# con-left-bot.net
KiCad netlist of a schematic drawn in Altium Designer
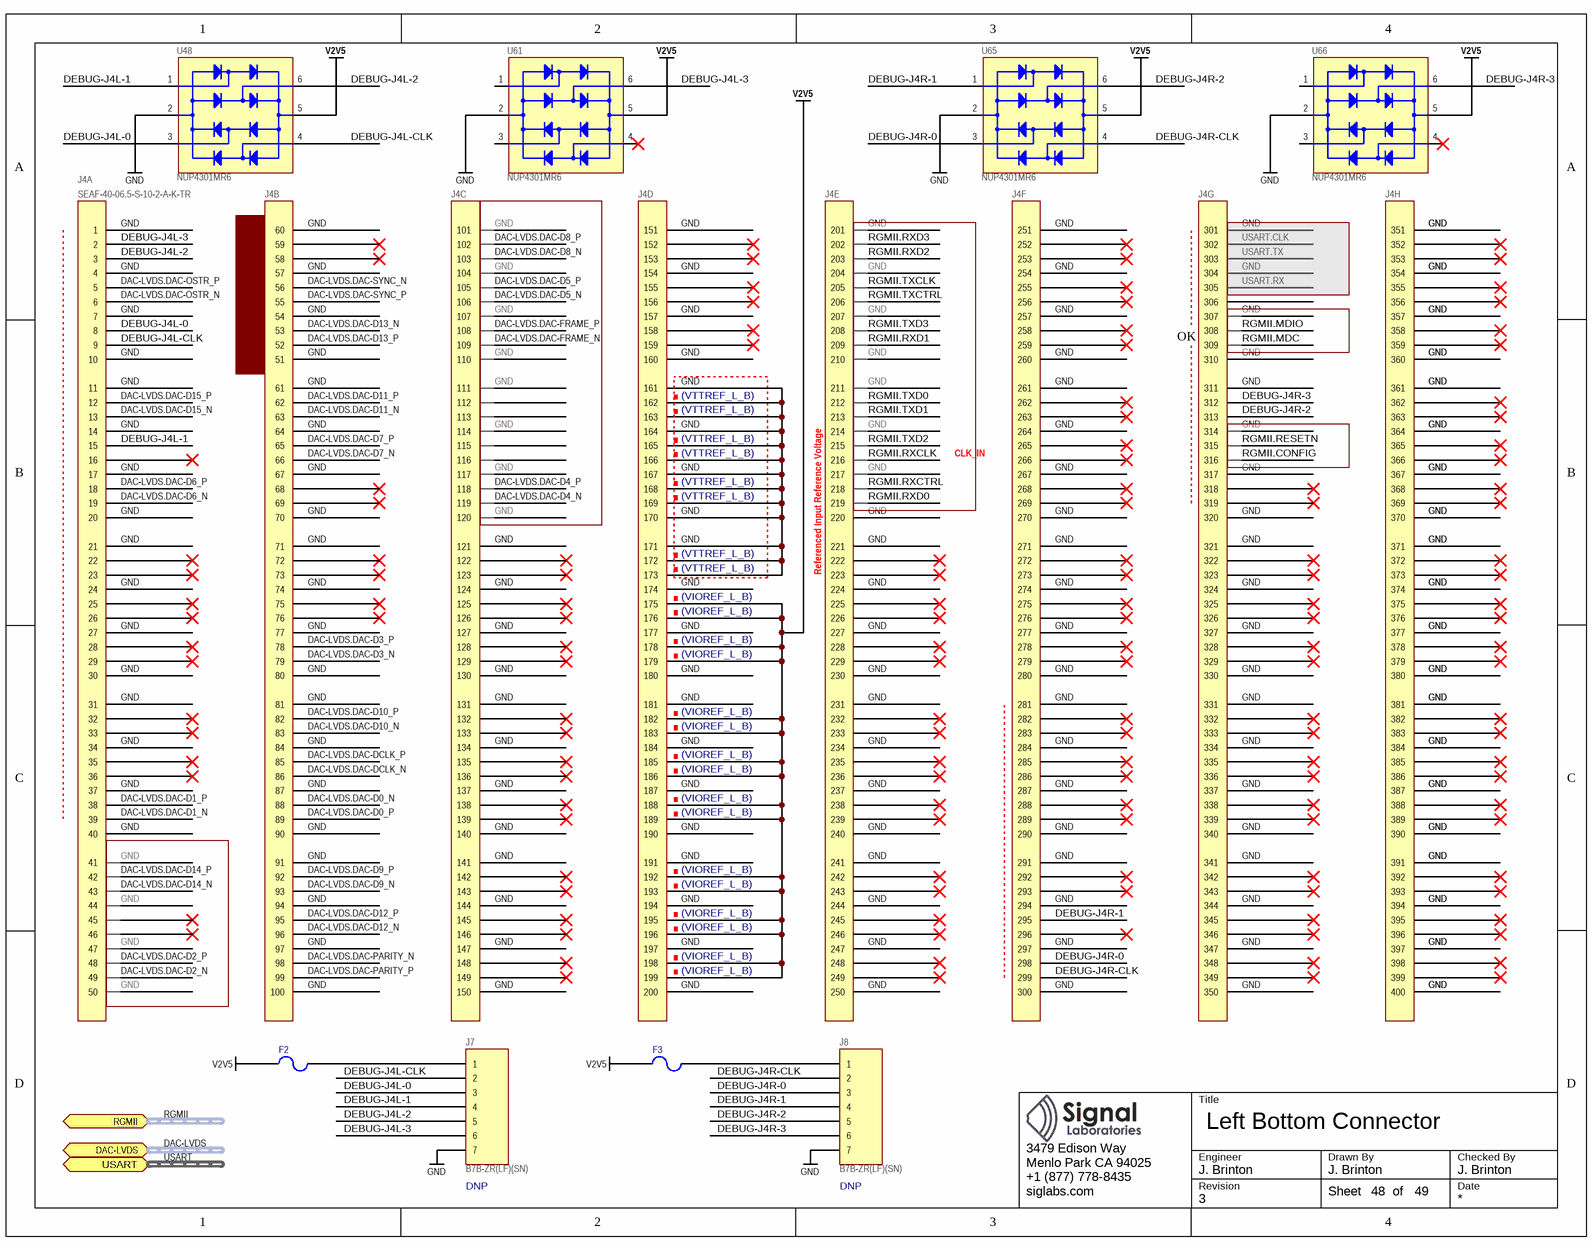
[diagram p0: con-left-bot.SchDoc]

(export (version "E")
  (design (tool "Eeschema 10.0.6"))
  (components
    (comp (ref "F2")
      (value "0ZCJ0020FF2E")
      (footprint "generic:1206")
      (description "PTC Resettable Fuse, 0.2A, 30V, SMD 1206")
      (fields (field (name "MANUFACTURER") "Bell Fuse"))
      (libsource (lib "bel-fuse") (part "0ZCJ0020FF2E"))
    )
    (comp (ref "F3")
      (value "0ZCJ0020FF2E")
      (footprint "generic:1206")
      (description "PTC Resettable Fuse, 0.2A, 30V, SMD 1206")
      (fields (field (name "MANUFACTURER") "Bell Fuse"))
      (libsource (lib "bel-fuse") (part "0ZCJ0020FF2E"))
    )
    (comp (ref "J4")
      (value "SEAF-40-06.5-S-10-2-A-K-TR")
      (footprint "samtec:SEAF-40-06.5-S-10-2-A-K-TR")
      (description "Terminal Array Assembly, Surface Mount, 0.050\" Pitch, 400 Pins")
      (fields (field (name "MANUFACTURER") "Samtec"))
      (libsource (lib "samtec") (part "SEAF-40-06.5-S-10-2-A-K-TR"))
    )
    (comp (ref "J7")
      (value "B7B-ZR(LF)(SN)")
      (footprint "jst:B7B-ZR")
      (description "Through-hole Shrouded Header 7-Position")
      (fields (field (name "MANUFACTURER") "JST") (field (name "DO NOT PLACE") "DNP"))
      (libsource (lib "jst") (part "B7B-ZR(LF)(SN)"))
    )
    (comp (ref "J8")
      (value "B7B-ZR(LF)(SN)")
      (footprint "jst:B7B-ZR")
      (description "Through-hole Shrouded Header 7-Position")
      (fields (field (name "MANUFACTURER") "JST") (field (name "DO NOT PLACE") "DNP"))
      (libsource (lib "jst") (part "B7B-ZR(LF)(SN)"))
    )
    (comp (ref "U48")
      (value "NUP4301MR6")
      (footprint "generic:SOT23-6")
      (description "4-Lane TVS Diode Array")
      (fields (field (name "MANUFACTURER") "On Semiconductor"))
      (libsource (lib "on_semi") (part "NUP4301MR6"))
    )
    (comp (ref "U61")
      (value "NUP4301MR6")
      (footprint "generic:SOT23-6")
      (description "4-Lane TVS Diode Array")
      (fields (field (name "MANUFACTURER") "On Semiconductor"))
      (libsource (lib "on_semi") (part "NUP4301MR6"))
    )
    (comp (ref "U65")
      (value "NUP4301MR6")
      (footprint "generic:SOT23-6")
      (description "4-Lane TVS Diode Array")
      (fields (field (name "MANUFACTURER") "On Semiconductor"))
      (libsource (lib "on_semi") (part "NUP4301MR6"))
    )
    (comp (ref "U66")
      (value "NUP4301MR6")
      (footprint "generic:SOT23-6")
      (description "4-Lane TVS Diode Array")
      (fields (field (name "MANUFACTURER") "On Semiconductor"))
      (libsource (lib "on_semi") (part "NUP4301MR6"))
    )
  )
  (nets
    (net (code "4") (name "/DAC-LVDS.DAC-D0_N") (class "Default")
      (node (ref "J4") (pin "88") (pinfunction "88_88") (pintype "passive"))
    )
    (net (code "5") (name "/DAC-LVDS.DAC-D0_P") (class "Default")
      (node (ref "J4") (pin "89") (pinfunction "89_89") (pintype "passive"))
    )
    (net (code "6") (name "/DAC-LVDS.DAC-D1_N") (class "Default")
      (node (ref "J4") (pin "39") (pinfunction "39_39") (pintype "passive"))
    )
    (net (code "7") (name "/DAC-LVDS.DAC-D1_P") (class "Default")
      (node (ref "J4") (pin "38") (pinfunction "38_38") (pintype "passive"))
    )
    (net (code "8") (name "/DAC-LVDS.DAC-D2_N") (class "Default")
      (node (ref "J4") (pin "49") (pinfunction "49_49") (pintype "passive"))
    )
    (net (code "9") (name "/DAC-LVDS.DAC-D2_P") (class "Default")
      (node (ref "J4") (pin "48") (pinfunction "48_48") (pintype "passive"))
    )
    (net (code "10") (name "/DAC-LVDS.DAC-D3_N") (class "Default")
      (node (ref "J4") (pin "79") (pinfunction "79_79") (pintype "passive"))
    )
    (net (code "11") (name "/DAC-LVDS.DAC-D3_P") (class "Default")
      (node (ref "J4") (pin "78") (pinfunction "78_78") (pintype "passive"))
    )
    (net (code "12") (name "/DAC-LVDS.DAC-D4_N") (class "Default")
      (node (ref "J4") (pin "119") (pinfunction "119_119") (pintype "passive"))
    )
    (net (code "13") (name "/DAC-LVDS.DAC-D4_P") (class "Default")
      (node (ref "J4") (pin "118") (pinfunction "118_118") (pintype "passive"))
    )
    (net (code "14") (name "/DAC-LVDS.DAC-D5_N") (class "Default")
      (node (ref "J4") (pin "106") (pinfunction "106_106") (pintype "passive"))
    )
    (net (code "15") (name "/DAC-LVDS.DAC-D5_P") (class "Default")
      (node (ref "J4") (pin "105") (pinfunction "105_105") (pintype "passive"))
    )
    (net (code "16") (name "/DAC-LVDS.DAC-D6_N") (class "Default")
      (node (ref "J4") (pin "19") (pinfunction "19_19") (pintype "passive"))
    )
    (net (code "17") (name "/DAC-LVDS.DAC-D6_P") (class "Default")
      (node (ref "J4") (pin "18") (pinfunction "18_18") (pintype "passive"))
    )
    (net (code "18") (name "/DAC-LVDS.DAC-D7_N") (class "Default")
      (node (ref "J4") (pin "66") (pinfunction "66_66") (pintype "passive"))
    )
    (net (code "19") (name "/DAC-LVDS.DAC-D7_P") (class "Default")
      (node (ref "J4") (pin "65") (pinfunction "65_65") (pintype "passive"))
    )
    (net (code "20") (name "/DAC-LVDS.DAC-D8_N") (class "Default")
      (node (ref "J4") (pin "103") (pinfunction "103_103") (pintype "passive"))
    )
    (net (code "21") (name "/DAC-LVDS.DAC-D8_P") (class "Default")
      (node (ref "J4") (pin "102") (pinfunction "102_102") (pintype "passive"))
    )
    (net (code "22") (name "/DAC-LVDS.DAC-D9_N") (class "Default")
      (node (ref "J4") (pin "93") (pinfunction "93_93") (pintype "passive"))
    )
    (net (code "23") (name "/DAC-LVDS.DAC-D9_P") (class "Default")
      (node (ref "J4") (pin "92") (pinfunction "92_92") (pintype "passive"))
    )
    (net (code "24") (name "/DAC-LVDS.DAC-D10_N") (class "Default")
      (node (ref "J4") (pin "83") (pinfunction "83_83") (pintype "passive"))
    )
    (net (code "25") (name "/DAC-LVDS.DAC-D10_P") (class "Default")
      (node (ref "J4") (pin "82") (pinfunction "82_82") (pintype "passive"))
    )
    (net (code "26") (name "/DAC-LVDS.DAC-D11_N") (class "Default")
      (node (ref "J4") (pin "63") (pinfunction "63_63") (pintype "passive"))
    )
    (net (code "27") (name "/DAC-LVDS.DAC-D11_P") (class "Default")
      (node (ref "J4") (pin "62") (pinfunction "62_62") (pintype "passive"))
    )
    (net (code "28") (name "/DAC-LVDS.DAC-D12_N") (class "Default")
      (node (ref "J4") (pin "96") (pinfunction "96_96") (pintype "passive"))
    )
    (net (code "29") (name "/DAC-LVDS.DAC-D12_P") (class "Default")
      (node (ref "J4") (pin "95") (pinfunction "95_95") (pintype "passive"))
    )
    (net (code "30") (name "/DAC-LVDS.DAC-D13_N") (class "Default")
      (node (ref "J4") (pin "53") (pinfunction "53_53") (pintype "passive"))
    )
    (net (code "31") (name "/DAC-LVDS.DAC-D13_P") (class "Default")
      (node (ref "J4") (pin "52") (pinfunction "52_52") (pintype "passive"))
    )
    (net (code "32") (name "/DAC-LVDS.DAC-D14_N") (class "Default")
      (node (ref "J4") (pin "43") (pinfunction "43_43") (pintype "passive"))
    )
    (net (code "33") (name "/DAC-LVDS.DAC-D14_P") (class "Default")
      (node (ref "J4") (pin "42") (pinfunction "42_42") (pintype "passive"))
    )
    (net (code "34") (name "/DAC-LVDS.DAC-D15_N") (class "Default")
      (node (ref "J4") (pin "13") (pinfunction "13_13") (pintype "passive"))
    )
    (net (code "35") (name "/DAC-LVDS.DAC-D15_P") (class "Default")
      (node (ref "J4") (pin "12") (pinfunction "12_12") (pintype "passive"))
    )
    (net (code "36") (name "/DAC-LVDS.DAC-DCLK_N") (class "Default")
      (node (ref "J4") (pin "86") (pinfunction "86_86") (pintype "passive"))
    )
    (net (code "37") (name "/DAC-LVDS.DAC-DCLK_P") (class "Default")
      (node (ref "J4") (pin "85") (pinfunction "85_85") (pintype "passive"))
    )
    (net (code "38") (name "/DAC-LVDS.DAC-FRAME_N") (class "Default")
      (node (ref "J4") (pin "109") (pinfunction "109_109") (pintype "passive"))
    )
    (net (code "39") (name "/DAC-LVDS.DAC-FRAME_P") (class "Default")
      (node (ref "J4") (pin "108") (pinfunction "108_108") (pintype "passive"))
    )
    (net (code "40") (name "/DAC-LVDS.DAC-OSTR_N") (class "Default")
      (node (ref "J4") (pin "6") (pinfunction "6_6") (pintype "passive"))
    )
    (net (code "41") (name "/DAC-LVDS.DAC-OSTR_P") (class "Default")
      (node (ref "J4") (pin "5") (pinfunction "5_5") (pintype "passive"))
    )
    (net (code "42") (name "/DAC-LVDS.DAC-PARITY_N") (class "Default")
      (node (ref "J4") (pin "98") (pinfunction "98_98") (pintype "passive"))
    )
    (net (code "43") (name "/DAC-LVDS.DAC-PARITY_P") (class "Default")
      (node (ref "J4") (pin "99") (pinfunction "99_99") (pintype "passive"))
    )
    (net (code "44") (name "/DAC-LVDS.DAC-SYNC_N") (class "Default")
      (node (ref "J4") (pin "56") (pinfunction "56_56") (pintype "passive"))
    )
    (net (code "45") (name "/DAC-LVDS.DAC-SYNC_P") (class "Default")
      (node (ref "J4") (pin "55") (pinfunction "55_55") (pintype "passive"))
    )
    (net (code "46") (name "/DEBUG-J4L-0") (class "Default")
      (node (ref "J4") (pin "8") (pinfunction "8_8") (pintype "passive"))
      (node (ref "J7") (pin "3") (pinfunction "3_3") (pintype "passive"))
      (node (ref "U48") (pin "3") (pinfunction "B_3") (pintype "passive"))
    )
    (net (code "47") (name "/DEBUG-J4L-1") (class "Default")
      (node (ref "J4") (pin "15") (pinfunction "15_15") (pintype "passive"))
      (node (ref "J7") (pin "4") (pinfunction "4_4") (pintype "passive"))
      (node (ref "U48") (pin "1") (pinfunction "A_1") (pintype "passive"))
    )
    (net (code "48") (name "/DEBUG-J4L-2") (class "Default")
      (node (ref "J4") (pin "3") (pinfunction "3_3") (pintype "passive"))
      (node (ref "J7") (pin "5") (pinfunction "5_5") (pintype "passive"))
      (node (ref "U48") (pin "6") (pinfunction "D_6") (pintype "passive"))
    )
    (net (code "49") (name "/DEBUG-J4L-3") (class "Default")
      (node (ref "J4") (pin "2") (pinfunction "2_2") (pintype "passive"))
      (node (ref "J7") (pin "6") (pinfunction "6_6") (pintype "passive"))
      (node (ref "U61") (pin "6") (pinfunction "D_6") (pintype "passive"))
    )
    (net (code "50") (name "/DEBUG-J4L-CLK") (class "Default")
      (node (ref "J4") (pin "9") (pinfunction "9_9") (pintype "passive"))
      (node (ref "J7") (pin "2") (pinfunction "2_2") (pintype "passive"))
      (node (ref "U48") (pin "4") (pinfunction "C_4") (pintype "passive"))
    )
    (net (code "51") (name "/DEBUG-J4R-0") (class "Default")
      (node (ref "J4") (pin "298") (pinfunction "298_298") (pintype "passive"))
      (node (ref "J8") (pin "3") (pinfunction "3_3") (pintype "passive"))
      (node (ref "U65") (pin "3") (pinfunction "B_3") (pintype "passive"))
    )
    (net (code "52") (name "/DEBUG-J4R-1") (class "Default")
      (node (ref "J4") (pin "295") (pinfunction "295_295") (pintype "passive"))
      (node (ref "J8") (pin "4") (pinfunction "4_4") (pintype "passive"))
      (node (ref "U65") (pin "1") (pinfunction "A_1") (pintype "passive"))
    )
    (net (code "53") (name "/DEBUG-J4R-2") (class "Default")
      (node (ref "J4") (pin "313") (pinfunction "313_313") (pintype "passive"))
      (node (ref "J8") (pin "5") (pinfunction "5_5") (pintype "passive"))
      (node (ref "U65") (pin "6") (pinfunction "D_6") (pintype "passive"))
    )
    (net (code "54") (name "/DEBUG-J4R-3") (class "Default")
      (node (ref "J4") (pin "312") (pinfunction "312_312") (pintype "passive"))
      (node (ref "J8") (pin "6") (pinfunction "6_6") (pintype "passive"))
      (node (ref "U66") (pin "6") (pinfunction "D_6") (pintype "passive"))
    )
    (net (code "55") (name "/DEBUG-J4R-CLK") (class "Default")
      (node (ref "J4") (pin "299") (pinfunction "299_299") (pintype "passive"))
      (node (ref "J8") (pin "2") (pinfunction "2_2") (pintype "passive"))
      (node (ref "U65") (pin "4") (pinfunction "C_4") (pintype "passive"))
    )
    (net (code "56") (name "/RGMII.CONFIG") (class "Default")
      (node (ref "J4") (pin "316") (pinfunction "316_316") (pintype "passive"))
    )
    (net (code "57") (name "/RGMII.MDC") (class "Default")
      (node (ref "J4") (pin "309") (pinfunction "309_309") (pintype "passive"))
    )
    (net (code "58") (name "/RGMII.MDIO") (class "Default")
      (node (ref "J4") (pin "308") (pinfunction "308_308") (pintype "passive"))
    )
    (net (code "59") (name "/RGMII.RESETN") (class "Default")
      (node (ref "J4") (pin "315") (pinfunction "315_315") (pintype "passive"))
    )
    (net (code "60") (name "/RGMII.RXCLK") (class "Default")
      (node (ref "J4") (pin "216") (pinfunction "216_216") (pintype "passive"))
    )
    (net (code "61") (name "/RGMII.RXCTRL") (class "Default")
      (node (ref "J4") (pin "218") (pinfunction "218_218") (pintype "passive"))
    )
    (net (code "62") (name "/RGMII.RXD0") (class "Default")
      (node (ref "J4") (pin "219") (pinfunction "219_219") (pintype "passive"))
    )
    (net (code "63") (name "/RGMII.RXD1") (class "Default")
      (node (ref "J4") (pin "209") (pinfunction "209_209") (pintype "passive"))
    )
    (net (code "64") (name "/RGMII.RXD2") (class "Default")
      (node (ref "J4") (pin "203") (pinfunction "203_203") (pintype "passive"))
    )
    (net (code "65") (name "/RGMII.RXD3") (class "Default")
      (node (ref "J4") (pin "202") (pinfunction "202_202") (pintype "passive"))
    )
    (net (code "66") (name "/RGMII.TXCLK") (class "Default")
      (node (ref "J4") (pin "205") (pinfunction "205_205") (pintype "passive"))
    )
    (net (code "67") (name "/RGMII.TXCTRL") (class "Default")
      (node (ref "J4") (pin "206") (pinfunction "206_206") (pintype "passive"))
    )
    (net (code "68") (name "/RGMII.TXD0") (class "Default")
      (node (ref "J4") (pin "212") (pinfunction "212_212") (pintype "passive"))
    )
    (net (code "69") (name "/RGMII.TXD1") (class "Default")
      (node (ref "J4") (pin "213") (pinfunction "213_213") (pintype "passive"))
    )
    (net (code "70") (name "/RGMII.TXD2") (class "Default")
      (node (ref "J4") (pin "215") (pinfunction "215_215") (pintype "passive"))
    )
    (net (code "71") (name "/RGMII.TXD3") (class "Default")
      (node (ref "J4") (pin "208") (pinfunction "208_208") (pintype "passive"))
    )
    (net (code "72") (name "/USART.CLK") (class "Default")
      (node (ref "J4") (pin "302") (pinfunction "302_302") (pintype "passive"))
    )
    (net (code "73") (name "/USART.RX") (class "Default")
      (node (ref "J4") (pin "305") (pinfunction "305_305") (pintype "passive"))
    )
    (net (code "74") (name "/USART.TX") (class "Default")
      (node (ref "J4") (pin "303") (pinfunction "303_303") (pintype "passive"))
    )
    (net (code "78") (name "GND") (class "Default")
      (node (ref "J4") (pin "1") (pinfunction "1_1") (pintype "passive"))
      (node (ref "J4") (pin "10") (pinfunction "10_10") (pintype "passive"))
      (node (ref "J4") (pin "100") (pinfunction "100_100") (pintype "passive"))
      (node (ref "J4") (pin "101") (pinfunction "101_101") (pintype "passive"))
      (node (ref "J4") (pin "104") (pinfunction "104_104") (pintype "passive"))
      (node (ref "J4") (pin "107") (pinfunction "107_107") (pintype "passive"))
      (node (ref "J4") (pin "11") (pinfunction "11_11") (pintype "passive"))
      (node (ref "J4") (pin "110") (pinfunction "110_110") (pintype "passive"))
      (node (ref "J4") (pin "111") (pinfunction "111_111") (pintype "passive"))
      (node (ref "J4") (pin "114") (pinfunction "114_114") (pintype "passive"))
      (node (ref "J4") (pin "117") (pinfunction "117_117") (pintype "passive"))
      (node (ref "J4") (pin "120") (pinfunction "120_120") (pintype "passive"))
      (node (ref "J4") (pin "121") (pinfunction "121_121") (pintype "passive"))
      (node (ref "J4") (pin "124") (pinfunction "124_124") (pintype "passive"))
      (node (ref "J4") (pin "127") (pinfunction "127_127") (pintype "passive"))
      (node (ref "J4") (pin "130") (pinfunction "130_130") (pintype "passive"))
      (node (ref "J4") (pin "131") (pinfunction "131_131") (pintype "passive"))
      (node (ref "J4") (pin "134") (pinfunction "134_134") (pintype "passive"))
      (node (ref "J4") (pin "137") (pinfunction "137_137") (pintype "passive"))
      (node (ref "J4") (pin "14") (pinfunction "14_14") (pintype "passive"))
      (node (ref "J4") (pin "140") (pinfunction "140_140") (pintype "passive"))
      (node (ref "J4") (pin "141") (pinfunction "141_141") (pintype "passive"))
      (node (ref "J4") (pin "144") (pinfunction "144_144") (pintype "passive"))
      (node (ref "J4") (pin "147") (pinfunction "147_147") (pintype "passive"))
      (node (ref "J4") (pin "150") (pinfunction "150_150") (pintype "passive"))
      (node (ref "J4") (pin "151") (pinfunction "151_151") (pintype "passive"))
      (node (ref "J4") (pin "154") (pinfunction "154_154") (pintype "passive"))
      (node (ref "J4") (pin "157") (pinfunction "157_157") (pintype "passive"))
      (node (ref "J4") (pin "160") (pinfunction "160_160") (pintype "passive"))
      (node (ref "J4") (pin "161") (pinfunction "161_161") (pintype "passive"))
      (node (ref "J4") (pin "162") (pinfunction "162_162") (pintype "passive"))
      (node (ref "J4") (pin "163") (pinfunction "163_163") (pintype "passive"))
      (node (ref "J4") (pin "164") (pinfunction "164_164") (pintype "passive"))
      (node (ref "J4") (pin "165") (pinfunction "165_165") (pintype "passive"))
      (node (ref "J4") (pin "166") (pinfunction "166_166") (pintype "passive"))
      (node (ref "J4") (pin "167") (pinfunction "167_167") (pintype "passive"))
      (node (ref "J4") (pin "168") (pinfunction "168_168") (pintype "passive"))
      (node (ref "J4") (pin "169") (pinfunction "169_169") (pintype "passive"))
      (node (ref "J4") (pin "17") (pinfunction "17_17") (pintype "passive"))
      (node (ref "J4") (pin "170") (pinfunction "170_170") (pintype "passive"))
      (node (ref "J4") (pin "171") (pinfunction "171_171") (pintype "passive"))
      (node (ref "J4") (pin "172") (pinfunction "172_172") (pintype "passive"))
      (node (ref "J4") (pin "173") (pinfunction "173_173") (pintype "passive"))
      (node (ref "J4") (pin "174") (pinfunction "174_174") (pintype "passive"))
      (node (ref "J4") (pin "177") (pinfunction "177_177") (pintype "passive"))
      (node (ref "J4") (pin "180") (pinfunction "180_180") (pintype "passive"))
      (node (ref "J4") (pin "181") (pinfunction "181_181") (pintype "passive"))
      (node (ref "J4") (pin "184") (pinfunction "184_184") (pintype "passive"))
      (node (ref "J4") (pin "187") (pinfunction "187_187") (pintype "passive"))
      (node (ref "J4") (pin "190") (pinfunction "190_190") (pintype "passive"))
      (node (ref "J4") (pin "191") (pinfunction "191_191") (pintype "passive"))
      (node (ref "J4") (pin "194") (pinfunction "194_194") (pintype "passive"))
      (node (ref "J4") (pin "197") (pinfunction "197_197") (pintype "passive"))
      (node (ref "J4") (pin "20") (pinfunction "20_20") (pintype "passive"))
      (node (ref "J4") (pin "200") (pinfunction "200_200") (pintype "passive"))
      (node (ref "J4") (pin "201") (pinfunction "201_201") (pintype "passive"))
      (node (ref "J4") (pin "204") (pinfunction "204_204") (pintype "passive"))
      (node (ref "J4") (pin "207") (pinfunction "207_207") (pintype "passive"))
      (node (ref "J4") (pin "21") (pinfunction "21_21") (pintype "passive"))
      (node (ref "J4") (pin "210") (pinfunction "210_210") (pintype "passive"))
      (node (ref "J4") (pin "211") (pinfunction "211_211") (pintype "passive"))
      (node (ref "J4") (pin "214") (pinfunction "214_214") (pintype "passive"))
      (node (ref "J4") (pin "217") (pinfunction "217_217") (pintype "passive"))
      (node (ref "J4") (pin "220") (pinfunction "220_220") (pintype "passive"))
      (node (ref "J4") (pin "221") (pinfunction "221_221") (pintype "passive"))
      (node (ref "J4") (pin "224") (pinfunction "224_224") (pintype "passive"))
      (node (ref "J4") (pin "227") (pinfunction "227_227") (pintype "passive"))
      (node (ref "J4") (pin "230") (pinfunction "230_230") (pintype "passive"))
      (node (ref "J4") (pin "231") (pinfunction "231_231") (pintype "passive"))
      (node (ref "J4") (pin "234") (pinfunction "234_234") (pintype "passive"))
      (node (ref "J4") (pin "237") (pinfunction "237_237") (pintype "passive"))
      (node (ref "J4") (pin "24") (pinfunction "24_24") (pintype "passive"))
      (node (ref "J4") (pin "240") (pinfunction "240_240") (pintype "passive"))
      (node (ref "J4") (pin "241") (pinfunction "241_241") (pintype "passive"))
      (node (ref "J4") (pin "244") (pinfunction "244_244") (pintype "passive"))
      (node (ref "J4") (pin "247") (pinfunction "247_247") (pintype "passive"))
      (node (ref "J4") (pin "250") (pinfunction "250_250") (pintype "passive"))
      (node (ref "J4") (pin "251") (pinfunction "251_251") (pintype "passive"))
      (node (ref "J4") (pin "254") (pinfunction "254_254") (pintype "passive"))
      (node (ref "J4") (pin "257") (pinfunction "257_257") (pintype "passive"))
      (node (ref "J4") (pin "260") (pinfunction "260_260") (pintype "passive"))
      (node (ref "J4") (pin "261") (pinfunction "261_261") (pintype "passive"))
      (node (ref "J4") (pin "264") (pinfunction "264_264") (pintype "passive"))
      (node (ref "J4") (pin "267") (pinfunction "267_267") (pintype "passive"))
      (node (ref "J4") (pin "27") (pinfunction "27_27") (pintype "passive"))
      (node (ref "J4") (pin "270") (pinfunction "270_270") (pintype "passive"))
      (node (ref "J4") (pin "271") (pinfunction "271_271") (pintype "passive"))
      (node (ref "J4") (pin "274") (pinfunction "274_274") (pintype "passive"))
      (node (ref "J4") (pin "277") (pinfunction "277_277") (pintype "passive"))
      (node (ref "J4") (pin "280") (pinfunction "280_280") (pintype "passive"))
      (node (ref "J4") (pin "281") (pinfunction "281_281") (pintype "passive"))
      (node (ref "J4") (pin "284") (pinfunction "284_284") (pintype "passive"))
      (node (ref "J4") (pin "287") (pinfunction "287_287") (pintype "passive"))
      (node (ref "J4") (pin "290") (pinfunction "290_290") (pintype "passive"))
      (node (ref "J4") (pin "291") (pinfunction "291_291") (pintype "passive"))
      (node (ref "J4") (pin "294") (pinfunction "294_294") (pintype "passive"))
      (node (ref "J4") (pin "297") (pinfunction "297_297") (pintype "passive"))
      (node (ref "J4") (pin "30") (pinfunction "30_30") (pintype "passive"))
      (node (ref "J4") (pin "300") (pinfunction "300_300") (pintype "passive"))
      (node (ref "J4") (pin "301") (pinfunction "301_301") (pintype "passive"))
      (node (ref "J4") (pin "304") (pinfunction "304_304") (pintype "passive"))
      (node (ref "J4") (pin "307") (pinfunction "307_307") (pintype "passive"))
      (node (ref "J4") (pin "31") (pinfunction "31_31") (pintype "passive"))
      (node (ref "J4") (pin "310") (pinfunction "310_310") (pintype "passive"))
      (node (ref "J4") (pin "311") (pinfunction "311_311") (pintype "passive"))
      (node (ref "J4") (pin "314") (pinfunction "314_314") (pintype "passive"))
      (node (ref "J4") (pin "317") (pinfunction "317_317") (pintype "passive"))
      (node (ref "J4") (pin "320") (pinfunction "320_320") (pintype "passive"))
      (node (ref "J4") (pin "321") (pinfunction "321_321") (pintype "passive"))
      (node (ref "J4") (pin "324") (pinfunction "324_324") (pintype "passive"))
      (node (ref "J4") (pin "327") (pinfunction "327_327") (pintype "passive"))
      (node (ref "J4") (pin "330") (pinfunction "330_330") (pintype "passive"))
      (node (ref "J4") (pin "331") (pinfunction "331_331") (pintype "passive"))
      (node (ref "J4") (pin "334") (pinfunction "334_334") (pintype "passive"))
      (node (ref "J4") (pin "337") (pinfunction "337_337") (pintype "passive"))
      (node (ref "J4") (pin "34") (pinfunction "34_34") (pintype "passive"))
      (node (ref "J4") (pin "340") (pinfunction "340_340") (pintype "passive"))
      (node (ref "J4") (pin "341") (pinfunction "341_341") (pintype "passive"))
      (node (ref "J4") (pin "344") (pinfunction "344_344") (pintype "passive"))
      (node (ref "J4") (pin "347") (pinfunction "347_347") (pintype "passive"))
      (node (ref "J4") (pin "350") (pinfunction "350_350") (pintype "passive"))
      (node (ref "J4") (pin "351") (pinfunction "351_351") (pintype "passive"))
      (node (ref "J4") (pin "354") (pinfunction "354_354") (pintype "passive"))
      (node (ref "J4") (pin "357") (pinfunction "357_357") (pintype "passive"))
      (node (ref "J4") (pin "360") (pinfunction "360_360") (pintype "passive"))
      (node (ref "J4") (pin "361") (pinfunction "361_361") (pintype "passive"))
      (node (ref "J4") (pin "364") (pinfunction "364_364") (pintype "passive"))
      (node (ref "J4") (pin "367") (pinfunction "367_367") (pintype "passive"))
      (node (ref "J4") (pin "37") (pinfunction "37_37") (pintype "passive"))
      (node (ref "J4") (pin "370") (pinfunction "370_370") (pintype "passive"))
      (node (ref "J4") (pin "371") (pinfunction "371_371") (pintype "passive"))
      (node (ref "J4") (pin "374") (pinfunction "374_374") (pintype "passive"))
      (node (ref "J4") (pin "377") (pinfunction "377_377") (pintype "passive"))
      (node (ref "J4") (pin "380") (pinfunction "380_380") (pintype "passive"))
      (node (ref "J4") (pin "381") (pinfunction "381_381") (pintype "passive"))
      (node (ref "J4") (pin "384") (pinfunction "384_384") (pintype "passive"))
      (node (ref "J4") (pin "387") (pinfunction "387_387") (pintype "passive"))
      (node (ref "J4") (pin "390") (pinfunction "390_390") (pintype "passive"))
      (node (ref "J4") (pin "391") (pinfunction "391_391") (pintype "passive"))
      (node (ref "J4") (pin "394") (pinfunction "394_394") (pintype "passive"))
      (node (ref "J4") (pin "397") (pinfunction "397_397") (pintype "passive"))
      (node (ref "J4") (pin "4") (pinfunction "4_4") (pintype "passive"))
      (node (ref "J4") (pin "40") (pinfunction "40_40") (pintype "passive"))
      (node (ref "J4") (pin "400") (pinfunction "400_400") (pintype "passive"))
      (node (ref "J4") (pin "41") (pinfunction "41_41") (pintype "passive"))
      (node (ref "J4") (pin "44") (pinfunction "44_44") (pintype "passive"))
      (node (ref "J4") (pin "47") (pinfunction "47_47") (pintype "passive"))
      (node (ref "J4") (pin "50") (pinfunction "50_50") (pintype "passive"))
      (node (ref "J4") (pin "51") (pinfunction "51_51") (pintype "passive"))
      (node (ref "J4") (pin "54") (pinfunction "54_54") (pintype "passive"))
      (node (ref "J4") (pin "57") (pinfunction "57_57") (pintype "passive"))
      (node (ref "J4") (pin "60") (pinfunction "60_60") (pintype "passive"))
      (node (ref "J4") (pin "61") (pinfunction "61_61") (pintype "passive"))
      (node (ref "J4") (pin "64") (pinfunction "64_64") (pintype "passive"))
      (node (ref "J4") (pin "67") (pinfunction "67_67") (pintype "passive"))
      (node (ref "J4") (pin "7") (pinfunction "7_7") (pintype "passive"))
      (node (ref "J4") (pin "70") (pinfunction "70_70") (pintype "passive"))
      (node (ref "J4") (pin "71") (pinfunction "71_71") (pintype "passive"))
      (node (ref "J4") (pin "74") (pinfunction "74_74") (pintype "passive"))
      (node (ref "J4") (pin "77") (pinfunction "77_77") (pintype "passive"))
      (node (ref "J4") (pin "80") (pinfunction "80_80") (pintype "passive"))
      (node (ref "J4") (pin "81") (pinfunction "81_81") (pintype "passive"))
      (node (ref "J4") (pin "84") (pinfunction "84_84") (pintype "passive"))
      (node (ref "J4") (pin "87") (pinfunction "87_87") (pintype "passive"))
      (node (ref "J4") (pin "90") (pinfunction "90_90") (pintype "passive"))
      (node (ref "J4") (pin "91") (pinfunction "91_91") (pintype "passive"))
      (node (ref "J4") (pin "94") (pinfunction "94_94") (pintype "passive"))
      (node (ref "J4") (pin "97") (pinfunction "97_97") (pintype "passive"))
      (node (ref "J7") (pin "7") (pinfunction "7_7") (pintype "passive"))
      (node (ref "J8") (pin "7") (pinfunction "7_7") (pintype "passive"))
      (node (ref "U48") (pin "2") (pinfunction "VN_2") (pintype "passive"))
      (node (ref "U61") (pin "2") (pinfunction "VN_2") (pintype "passive"))
      (node (ref "U65") (pin "2") (pinfunction "VN_2") (pintype "passive"))
      (node (ref "U66") (pin "2") (pinfunction "VN_2") (pintype "passive"))
    )
    (net (code "79") (name "Net-(F2-Pad1)") (class "Default")
      (node (ref "F2") (pin "1") (pinfunction "1_1") (pintype "passive"))
      (node (ref "J7") (pin "1") (pinfunction "1_1") (pintype "passive"))
    )
    (net (code "80") (name "Net-(F3-Pad1)") (class "Default")
      (node (ref "F3") (pin "1") (pinfunction "1_1") (pintype "passive"))
      (node (ref "J8") (pin "1") (pinfunction "1_1") (pintype "passive"))
    )
    (net (code "81") (name "V2V5") (class "Default")
      (node (ref "F2") (pin "2") (pinfunction "2_2") (pintype "passive"))
      (node (ref "F3") (pin "2") (pinfunction "2_2") (pintype "passive"))
      (node (ref "J4") (pin "175") (pinfunction "175_175") (pintype "passive"))
      (node (ref "J4") (pin "176") (pinfunction "176_176") (pintype "passive"))
      (node (ref "J4") (pin "178") (pinfunction "178_178") (pintype "passive"))
      (node (ref "J4") (pin "179") (pinfunction "179_179") (pintype "passive"))
      (node (ref "J4") (pin "182") (pinfunction "182_182") (pintype "passive"))
      (node (ref "J4") (pin "183") (pinfunction "183_183") (pintype "passive"))
      (node (ref "J4") (pin "185") (pinfunction "185_185") (pintype "passive"))
      (node (ref "J4") (pin "186") (pinfunction "186_186") (pintype "passive"))
      (node (ref "J4") (pin "188") (pinfunction "188_188") (pintype "passive"))
      (node (ref "J4") (pin "189") (pinfunction "189_189") (pintype "passive"))
      (node (ref "J4") (pin "192") (pinfunction "192_192") (pintype "passive"))
      (node (ref "J4") (pin "193") (pinfunction "193_193") (pintype "passive"))
      (node (ref "J4") (pin "195") (pinfunction "195_195") (pintype "passive"))
      (node (ref "J4") (pin "196") (pinfunction "196_196") (pintype "passive"))
      (node (ref "J4") (pin "198") (pinfunction "198_198") (pintype "passive"))
      (node (ref "J4") (pin "199") (pinfunction "199_199") (pintype "passive"))
      (node (ref "U48") (pin "5") (pinfunction "VP_5") (pintype "passive"))
      (node (ref "U61") (pin "5") (pinfunction "VP_5") (pintype "passive"))
      (node (ref "U65") (pin "5") (pinfunction "VP_5") (pintype "passive"))
      (node (ref "U66") (pin "5") (pinfunction "VP_5") (pintype "passive"))
    )
    (net (code "82") (name "unconnected-(J4-Pad16)") (class "Default")
      (node (ref "J4") (pin "16") (pinfunction "16_16") (pintype "passive+no_connect"))
    )
    (net (code "83") (name "unconnected-(J4-Pad22)") (class "Default")
      (node (ref "J4") (pin "22") (pinfunction "22_22") (pintype "passive+no_connect"))
    )
    (net (code "84") (name "unconnected-(J4-Pad23)") (class "Default")
      (node (ref "J4") (pin "23") (pinfunction "23_23") (pintype "passive+no_connect"))
    )
    (net (code "85") (name "unconnected-(J4-Pad25)") (class "Default")
      (node (ref "J4") (pin "25") (pinfunction "25_25") (pintype "passive+no_connect"))
    )
    (net (code "86") (name "unconnected-(J4-Pad26)") (class "Default")
      (node (ref "J4") (pin "26") (pinfunction "26_26") (pintype "passive+no_connect"))
    )
    (net (code "87") (name "unconnected-(J4-Pad28)") (class "Default")
      (node (ref "J4") (pin "28") (pinfunction "28_28") (pintype "passive+no_connect"))
    )
    (net (code "88") (name "unconnected-(J4-Pad29)") (class "Default")
      (node (ref "J4") (pin "29") (pinfunction "29_29") (pintype "passive+no_connect"))
    )
    (net (code "89") (name "unconnected-(J4-Pad32)") (class "Default")
      (node (ref "J4") (pin "32") (pinfunction "32_32") (pintype "passive+no_connect"))
    )
    (net (code "90") (name "unconnected-(J4-Pad33)") (class "Default")
      (node (ref "J4") (pin "33") (pinfunction "33_33") (pintype "passive+no_connect"))
    )
    (net (code "91") (name "unconnected-(J4-Pad35)") (class "Default")
      (node (ref "J4") (pin "35") (pinfunction "35_35") (pintype "passive+no_connect"))
    )
    (net (code "92") (name "unconnected-(J4-Pad36)") (class "Default")
      (node (ref "J4") (pin "36") (pinfunction "36_36") (pintype "passive+no_connect"))
    )
    (net (code "93") (name "unconnected-(J4-Pad45)") (class "Default")
      (node (ref "J4") (pin "45") (pinfunction "45_45") (pintype "passive+no_connect"))
    )
    (net (code "94") (name "unconnected-(J4-Pad46)") (class "Default")
      (node (ref "J4") (pin "46") (pinfunction "46_46") (pintype "passive+no_connect"))
    )
    (net (code "95") (name "unconnected-(J4-Pad58)") (class "Default")
      (node (ref "J4") (pin "58") (pinfunction "58_58") (pintype "passive+no_connect"))
    )
    (net (code "96") (name "unconnected-(J4-Pad59)") (class "Default")
      (node (ref "J4") (pin "59") (pinfunction "59_59") (pintype "passive+no_connect"))
    )
    (net (code "97") (name "unconnected-(J4-Pad68)") (class "Default")
      (node (ref "J4") (pin "68") (pinfunction "68_68") (pintype "passive+no_connect"))
    )
    (net (code "98") (name "unconnected-(J4-Pad69)") (class "Default")
      (node (ref "J4") (pin "69") (pinfunction "69_69") (pintype "passive+no_connect"))
    )
    (net (code "99") (name "unconnected-(J4-Pad72)") (class "Default")
      (node (ref "J4") (pin "72") (pinfunction "72_72") (pintype "passive+no_connect"))
    )
    (net (code "100") (name "unconnected-(J4-Pad73)") (class "Default")
      (node (ref "J4") (pin "73") (pinfunction "73_73") (pintype "passive+no_connect"))
    )
    (net (code "101") (name "unconnected-(J4-Pad75)") (class "Default")
      (node (ref "J4") (pin "75") (pinfunction "75_75") (pintype "passive+no_connect"))
    )
    (net (code "102") (name "unconnected-(J4-Pad76)") (class "Default")
      (node (ref "J4") (pin "76") (pinfunction "76_76") (pintype "passive+no_connect"))
    )
    (net (code "103") (name "unconnected-(J4-Pad112)") (class "Default")
      (node (ref "J4") (pin "112") (pinfunction "112_112") (pintype "passive"))
    )
    (net (code "104") (name "unconnected-(J4-Pad113)") (class "Default")
      (node (ref "J4") (pin "113") (pinfunction "113_113") (pintype "passive"))
    )
    (net (code "105") (name "unconnected-(J4-Pad115)") (class "Default")
      (node (ref "J4") (pin "115") (pinfunction "115_115") (pintype "passive"))
    )
    (net (code "106") (name "unconnected-(J4-Pad116)") (class "Default")
      (node (ref "J4") (pin "116") (pinfunction "116_116") (pintype "passive"))
    )
    (net (code "107") (name "unconnected-(J4-Pad122)") (class "Default")
      (node (ref "J4") (pin "122") (pinfunction "122_122") (pintype "passive+no_connect"))
    )
    (net (code "108") (name "unconnected-(J4-Pad123)") (class "Default")
      (node (ref "J4") (pin "123") (pinfunction "123_123") (pintype "passive+no_connect"))
    )
    (net (code "109") (name "unconnected-(J4-Pad125)") (class "Default")
      (node (ref "J4") (pin "125") (pinfunction "125_125") (pintype "passive+no_connect"))
    )
    (net (code "110") (name "unconnected-(J4-Pad126)") (class "Default")
      (node (ref "J4") (pin "126") (pinfunction "126_126") (pintype "passive+no_connect"))
    )
    (net (code "111") (name "unconnected-(J4-Pad128)") (class "Default")
      (node (ref "J4") (pin "128") (pinfunction "128_128") (pintype "passive+no_connect"))
    )
    (net (code "112") (name "unconnected-(J4-Pad129)") (class "Default")
      (node (ref "J4") (pin "129") (pinfunction "129_129") (pintype "passive+no_connect"))
    )
    (net (code "113") (name "unconnected-(J4-Pad132)") (class "Default")
      (node (ref "J4") (pin "132") (pinfunction "132_132") (pintype "passive+no_connect"))
    )
    (net (code "114") (name "unconnected-(J4-Pad133)") (class "Default")
      (node (ref "J4") (pin "133") (pinfunction "133_133") (pintype "passive+no_connect"))
    )
    (net (code "115") (name "unconnected-(J4-Pad135)") (class "Default")
      (node (ref "J4") (pin "135") (pinfunction "135_135") (pintype "passive+no_connect"))
    )
    (net (code "116") (name "unconnected-(J4-Pad136)") (class "Default")
      (node (ref "J4") (pin "136") (pinfunction "136_136") (pintype "passive+no_connect"))
    )
    (net (code "117") (name "unconnected-(J4-Pad138)") (class "Default")
      (node (ref "J4") (pin "138") (pinfunction "138_138") (pintype "passive+no_connect"))
    )
    (net (code "118") (name "unconnected-(J4-Pad139)") (class "Default")
      (node (ref "J4") (pin "139") (pinfunction "139_139") (pintype "passive+no_connect"))
    )
    (net (code "119") (name "unconnected-(J4-Pad142)") (class "Default")
      (node (ref "J4") (pin "142") (pinfunction "142_142") (pintype "passive+no_connect"))
    )
    (net (code "120") (name "unconnected-(J4-Pad143)") (class "Default")
      (node (ref "J4") (pin "143") (pinfunction "143_143") (pintype "passive+no_connect"))
    )
    (net (code "121") (name "unconnected-(J4-Pad145)") (class "Default")
      (node (ref "J4") (pin "145") (pinfunction "145_145") (pintype "passive+no_connect"))
    )
    (net (code "122") (name "unconnected-(J4-Pad146)") (class "Default")
      (node (ref "J4") (pin "146") (pinfunction "146_146") (pintype "passive+no_connect"))
    )
    (net (code "123") (name "unconnected-(J4-Pad148)") (class "Default")
      (node (ref "J4") (pin "148") (pinfunction "148_148") (pintype "passive+no_connect"))
    )
    (net (code "124") (name "unconnected-(J4-Pad149)") (class "Default")
      (node (ref "J4") (pin "149") (pinfunction "149_149") (pintype "passive+no_connect"))
    )
    (net (code "125") (name "unconnected-(J4-Pad152)") (class "Default")
      (node (ref "J4") (pin "152") (pinfunction "152_152") (pintype "passive+no_connect"))
    )
    (net (code "126") (name "unconnected-(J4-Pad153)") (class "Default")
      (node (ref "J4") (pin "153") (pinfunction "153_153") (pintype "passive+no_connect"))
    )
    (net (code "127") (name "unconnected-(J4-Pad155)") (class "Default")
      (node (ref "J4") (pin "155") (pinfunction "155_155") (pintype "passive+no_connect"))
    )
    (net (code "128") (name "unconnected-(J4-Pad156)") (class "Default")
      (node (ref "J4") (pin "156") (pinfunction "156_156") (pintype "passive+no_connect"))
    )
    (net (code "129") (name "unconnected-(J4-Pad158)") (class "Default")
      (node (ref "J4") (pin "158") (pinfunction "158_158") (pintype "passive+no_connect"))
    )
    (net (code "130") (name "unconnected-(J4-Pad159)") (class "Default")
      (node (ref "J4") (pin "159") (pinfunction "159_159") (pintype "passive+no_connect"))
    )
    (net (code "131") (name "unconnected-(J4-Pad222)") (class "Default")
      (node (ref "J4") (pin "222") (pinfunction "222_222") (pintype "passive+no_connect"))
    )
    (net (code "132") (name "unconnected-(J4-Pad223)") (class "Default")
      (node (ref "J4") (pin "223") (pinfunction "223_223") (pintype "passive+no_connect"))
    )
    (net (code "133") (name "unconnected-(J4-Pad225)") (class "Default")
      (node (ref "J4") (pin "225") (pinfunction "225_225") (pintype "passive+no_connect"))
    )
    (net (code "134") (name "unconnected-(J4-Pad226)") (class "Default")
      (node (ref "J4") (pin "226") (pinfunction "226_226") (pintype "passive+no_connect"))
    )
    (net (code "135") (name "unconnected-(J4-Pad228)") (class "Default")
      (node (ref "J4") (pin "228") (pinfunction "228_228") (pintype "passive+no_connect"))
    )
    (net (code "136") (name "unconnected-(J4-Pad229)") (class "Default")
      (node (ref "J4") (pin "229") (pinfunction "229_229") (pintype "passive+no_connect"))
    )
    (net (code "137") (name "unconnected-(J4-Pad232)") (class "Default")
      (node (ref "J4") (pin "232") (pinfunction "232_232") (pintype "passive+no_connect"))
    )
    (net (code "138") (name "unconnected-(J4-Pad233)") (class "Default")
      (node (ref "J4") (pin "233") (pinfunction "233_233") (pintype "passive+no_connect"))
    )
    (net (code "139") (name "unconnected-(J4-Pad235)") (class "Default")
      (node (ref "J4") (pin "235") (pinfunction "235_235") (pintype "passive+no_connect"))
    )
    (net (code "140") (name "unconnected-(J4-Pad236)") (class "Default")
      (node (ref "J4") (pin "236") (pinfunction "236_236") (pintype "passive+no_connect"))
    )
    (net (code "141") (name "unconnected-(J4-Pad238)") (class "Default")
      (node (ref "J4") (pin "238") (pinfunction "238_238") (pintype "passive+no_connect"))
    )
    (net (code "142") (name "unconnected-(J4-Pad239)") (class "Default")
      (node (ref "J4") (pin "239") (pinfunction "239_239") (pintype "passive+no_connect"))
    )
    (net (code "143") (name "unconnected-(J4-Pad242)") (class "Default")
      (node (ref "J4") (pin "242") (pinfunction "242_242") (pintype "passive+no_connect"))
    )
    (net (code "144") (name "unconnected-(J4-Pad243)") (class "Default")
      (node (ref "J4") (pin "243") (pinfunction "243_243") (pintype "passive+no_connect"))
    )
    (net (code "145") (name "unconnected-(J4-Pad245)") (class "Default")
      (node (ref "J4") (pin "245") (pinfunction "245_245") (pintype "passive+no_connect"))
    )
    (net (code "146") (name "unconnected-(J4-Pad246)") (class "Default")
      (node (ref "J4") (pin "246") (pinfunction "246_246") (pintype "passive+no_connect"))
    )
    (net (code "147") (name "unconnected-(J4-Pad248)") (class "Default")
      (node (ref "J4") (pin "248") (pinfunction "248_248") (pintype "passive+no_connect"))
    )
    (net (code "148") (name "unconnected-(J4-Pad249)") (class "Default")
      (node (ref "J4") (pin "249") (pinfunction "249_249") (pintype "passive+no_connect"))
    )
    (net (code "149") (name "unconnected-(J4-Pad252)") (class "Default")
      (node (ref "J4") (pin "252") (pinfunction "252_252") (pintype "passive+no_connect"))
    )
    (net (code "150") (name "unconnected-(J4-Pad253)") (class "Default")
      (node (ref "J4") (pin "253") (pinfunction "253_253") (pintype "passive+no_connect"))
    )
    (net (code "151") (name "unconnected-(J4-Pad255)") (class "Default")
      (node (ref "J4") (pin "255") (pinfunction "255_255") (pintype "passive+no_connect"))
    )
    (net (code "152") (name "unconnected-(J4-Pad256)") (class "Default")
      (node (ref "J4") (pin "256") (pinfunction "256_256") (pintype "passive+no_connect"))
    )
    (net (code "153") (name "unconnected-(J4-Pad258)") (class "Default")
      (node (ref "J4") (pin "258") (pinfunction "258_258") (pintype "passive+no_connect"))
    )
    (net (code "154") (name "unconnected-(J4-Pad259)") (class "Default")
      (node (ref "J4") (pin "259") (pinfunction "259_259") (pintype "passive+no_connect"))
    )
    (net (code "155") (name "unconnected-(J4-Pad262)") (class "Default")
      (node (ref "J4") (pin "262") (pinfunction "262_262") (pintype "passive+no_connect"))
    )
    (net (code "156") (name "unconnected-(J4-Pad263)") (class "Default")
      (node (ref "J4") (pin "263") (pinfunction "263_263") (pintype "passive+no_connect"))
    )
    (net (code "157") (name "unconnected-(J4-Pad265)") (class "Default")
      (node (ref "J4") (pin "265") (pinfunction "265_265") (pintype "passive+no_connect"))
    )
    (net (code "158") (name "unconnected-(J4-Pad266)") (class "Default")
      (node (ref "J4") (pin "266") (pinfunction "266_266") (pintype "passive+no_connect"))
    )
    (net (code "159") (name "unconnected-(J4-Pad268)") (class "Default")
      (node (ref "J4") (pin "268") (pinfunction "268_268") (pintype "passive+no_connect"))
    )
    (net (code "160") (name "unconnected-(J4-Pad269)") (class "Default")
      (node (ref "J4") (pin "269") (pinfunction "269_269") (pintype "passive+no_connect"))
    )
    (net (code "161") (name "unconnected-(J4-Pad272)") (class "Default")
      (node (ref "J4") (pin "272") (pinfunction "272_272") (pintype "passive+no_connect"))
    )
    (net (code "162") (name "unconnected-(J4-Pad273)") (class "Default")
      (node (ref "J4") (pin "273") (pinfunction "273_273") (pintype "passive+no_connect"))
    )
    (net (code "163") (name "unconnected-(J4-Pad275)") (class "Default")
      (node (ref "J4") (pin "275") (pinfunction "275_275") (pintype "passive+no_connect"))
    )
    (net (code "164") (name "unconnected-(J4-Pad276)") (class "Default")
      (node (ref "J4") (pin "276") (pinfunction "276_276") (pintype "passive+no_connect"))
    )
    (net (code "165") (name "unconnected-(J4-Pad278)") (class "Default")
      (node (ref "J4") (pin "278") (pinfunction "278_278") (pintype "passive+no_connect"))
    )
    (net (code "166") (name "unconnected-(J4-Pad279)") (class "Default")
      (node (ref "J4") (pin "279") (pinfunction "279_279") (pintype "passive+no_connect"))
    )
    (net (code "167") (name "unconnected-(J4-Pad282)") (class "Default")
      (node (ref "J4") (pin "282") (pinfunction "282_282") (pintype "passive+no_connect"))
    )
    (net (code "168") (name "unconnected-(J4-Pad283)") (class "Default")
      (node (ref "J4") (pin "283") (pinfunction "283_283") (pintype "passive+no_connect"))
    )
    (net (code "169") (name "unconnected-(J4-Pad285)") (class "Default")
      (node (ref "J4") (pin "285") (pinfunction "285_285") (pintype "passive+no_connect"))
    )
    (net (code "170") (name "unconnected-(J4-Pad286)") (class "Default")
      (node (ref "J4") (pin "286") (pinfunction "286_286") (pintype "passive+no_connect"))
    )
    (net (code "171") (name "unconnected-(J4-Pad288)") (class "Default")
      (node (ref "J4") (pin "288") (pinfunction "288_288") (pintype "passive+no_connect"))
    )
    (net (code "172") (name "unconnected-(J4-Pad289)") (class "Default")
      (node (ref "J4") (pin "289") (pinfunction "289_289") (pintype "passive+no_connect"))
    )
    (net (code "173") (name "unconnected-(J4-Pad292)") (class "Default")
      (node (ref "J4") (pin "292") (pinfunction "292_292") (pintype "passive+no_connect"))
    )
    (net (code "174") (name "unconnected-(J4-Pad293)") (class "Default")
      (node (ref "J4") (pin "293") (pinfunction "293_293") (pintype "passive+no_connect"))
    )
    (net (code "175") (name "unconnected-(J4-Pad296)") (class "Default")
      (node (ref "J4") (pin "296") (pinfunction "296_296") (pintype "passive+no_connect"))
    )
    (net (code "176") (name "unconnected-(J4-Pad306)") (class "Default")
      (node (ref "J4") (pin "306") (pinfunction "306_306") (pintype "passive"))
    )
    (net (code "177") (name "unconnected-(J4-Pad318)") (class "Default")
      (node (ref "J4") (pin "318") (pinfunction "318_318") (pintype "passive+no_connect"))
    )
    (net (code "178") (name "unconnected-(J4-Pad319)") (class "Default")
      (node (ref "J4") (pin "319") (pinfunction "319_319") (pintype "passive+no_connect"))
    )
    (net (code "179") (name "unconnected-(J4-Pad322)") (class "Default")
      (node (ref "J4") (pin "322") (pinfunction "322_322") (pintype "passive+no_connect"))
    )
    (net (code "180") (name "unconnected-(J4-Pad323)") (class "Default")
      (node (ref "J4") (pin "323") (pinfunction "323_323") (pintype "passive+no_connect"))
    )
    (net (code "181") (name "unconnected-(J4-Pad325)") (class "Default")
      (node (ref "J4") (pin "325") (pinfunction "325_325") (pintype "passive+no_connect"))
    )
    (net (code "182") (name "unconnected-(J4-Pad326)") (class "Default")
      (node (ref "J4") (pin "326") (pinfunction "326_326") (pintype "passive+no_connect"))
    )
    (net (code "183") (name "unconnected-(J4-Pad328)") (class "Default")
      (node (ref "J4") (pin "328") (pinfunction "328_328") (pintype "passive+no_connect"))
    )
    (net (code "184") (name "unconnected-(J4-Pad329)") (class "Default")
      (node (ref "J4") (pin "329") (pinfunction "329_329") (pintype "passive+no_connect"))
    )
    (net (code "185") (name "unconnected-(J4-Pad332)") (class "Default")
      (node (ref "J4") (pin "332") (pinfunction "332_332") (pintype "passive+no_connect"))
    )
    (net (code "186") (name "unconnected-(J4-Pad333)") (class "Default")
      (node (ref "J4") (pin "333") (pinfunction "333_333") (pintype "passive+no_connect"))
    )
    (net (code "187") (name "unconnected-(J4-Pad335)") (class "Default")
      (node (ref "J4") (pin "335") (pinfunction "335_335") (pintype "passive+no_connect"))
    )
    (net (code "188") (name "unconnected-(J4-Pad336)") (class "Default")
      (node (ref "J4") (pin "336") (pinfunction "336_336") (pintype "passive+no_connect"))
    )
    (net (code "189") (name "unconnected-(J4-Pad338)") (class "Default")
      (node (ref "J4") (pin "338") (pinfunction "338_338") (pintype "passive+no_connect"))
    )
    (net (code "190") (name "unconnected-(J4-Pad339)") (class "Default")
      (node (ref "J4") (pin "339") (pinfunction "339_339") (pintype "passive+no_connect"))
    )
    (net (code "191") (name "unconnected-(J4-Pad342)") (class "Default")
      (node (ref "J4") (pin "342") (pinfunction "342_342") (pintype "passive+no_connect"))
    )
    (net (code "192") (name "unconnected-(J4-Pad343)") (class "Default")
      (node (ref "J4") (pin "343") (pinfunction "343_343") (pintype "passive+no_connect"))
    )
    (net (code "193") (name "unconnected-(J4-Pad345)") (class "Default")
      (node (ref "J4") (pin "345") (pinfunction "345_345") (pintype "passive+no_connect"))
    )
    (net (code "194") (name "unconnected-(J4-Pad346)") (class "Default")
      (node (ref "J4") (pin "346") (pinfunction "346_346") (pintype "passive+no_connect"))
    )
    (net (code "195") (name "unconnected-(J4-Pad348)") (class "Default")
      (node (ref "J4") (pin "348") (pinfunction "348_348") (pintype "passive+no_connect"))
    )
    (net (code "196") (name "unconnected-(J4-Pad349)") (class "Default")
      (node (ref "J4") (pin "349") (pinfunction "349_349") (pintype "passive+no_connect"))
    )
    (net (code "197") (name "unconnected-(J4-Pad352)") (class "Default")
      (node (ref "J4") (pin "352") (pinfunction "352_352") (pintype "passive+no_connect"))
    )
    (net (code "198") (name "unconnected-(J4-Pad353)") (class "Default")
      (node (ref "J4") (pin "353") (pinfunction "353_353") (pintype "passive+no_connect"))
    )
    (net (code "199") (name "unconnected-(J4-Pad355)") (class "Default")
      (node (ref "J4") (pin "355") (pinfunction "355_355") (pintype "passive+no_connect"))
    )
    (net (code "200") (name "unconnected-(J4-Pad356)") (class "Default")
      (node (ref "J4") (pin "356") (pinfunction "356_356") (pintype "passive+no_connect"))
    )
    (net (code "201") (name "unconnected-(J4-Pad358)") (class "Default")
      (node (ref "J4") (pin "358") (pinfunction "358_358") (pintype "passive+no_connect"))
    )
    (net (code "202") (name "unconnected-(J4-Pad359)") (class "Default")
      (node (ref "J4") (pin "359") (pinfunction "359_359") (pintype "passive+no_connect"))
    )
    (net (code "203") (name "unconnected-(J4-Pad362)") (class "Default")
      (node (ref "J4") (pin "362") (pinfunction "362_362") (pintype "passive+no_connect"))
    )
    (net (code "204") (name "unconnected-(J4-Pad363)") (class "Default")
      (node (ref "J4") (pin "363") (pinfunction "363_363") (pintype "passive+no_connect"))
    )
    (net (code "205") (name "unconnected-(J4-Pad365)") (class "Default")
      (node (ref "J4") (pin "365") (pinfunction "365_365") (pintype "passive+no_connect"))
    )
    (net (code "206") (name "unconnected-(J4-Pad366)") (class "Default")
      (node (ref "J4") (pin "366") (pinfunction "366_366") (pintype "passive+no_connect"))
    )
    (net (code "207") (name "unconnected-(J4-Pad368)") (class "Default")
      (node (ref "J4") (pin "368") (pinfunction "368_368") (pintype "passive+no_connect"))
    )
    (net (code "208") (name "unconnected-(J4-Pad369)") (class "Default")
      (node (ref "J4") (pin "369") (pinfunction "369_369") (pintype "passive+no_connect"))
    )
    (net (code "209") (name "unconnected-(J4-Pad372)") (class "Default")
      (node (ref "J4") (pin "372") (pinfunction "372_372") (pintype "passive+no_connect"))
    )
    (net (code "210") (name "unconnected-(J4-Pad373)") (class "Default")
      (node (ref "J4") (pin "373") (pinfunction "373_373") (pintype "passive+no_connect"))
    )
    (net (code "211") (name "unconnected-(J4-Pad375)") (class "Default")
      (node (ref "J4") (pin "375") (pinfunction "375_375") (pintype "passive+no_connect"))
    )
    (net (code "212") (name "unconnected-(J4-Pad376)") (class "Default")
      (node (ref "J4") (pin "376") (pinfunction "376_376") (pintype "passive+no_connect"))
    )
    (net (code "213") (name "unconnected-(J4-Pad378)") (class "Default")
      (node (ref "J4") (pin "378") (pinfunction "378_378") (pintype "passive+no_connect"))
    )
    (net (code "214") (name "unconnected-(J4-Pad379)") (class "Default")
      (node (ref "J4") (pin "379") (pinfunction "379_379") (pintype "passive+no_connect"))
    )
    (net (code "215") (name "unconnected-(J4-Pad382)") (class "Default")
      (node (ref "J4") (pin "382") (pinfunction "382_382") (pintype "passive+no_connect"))
    )
    (net (code "216") (name "unconnected-(J4-Pad383)") (class "Default")
      (node (ref "J4") (pin "383") (pinfunction "383_383") (pintype "passive+no_connect"))
    )
    (net (code "217") (name "unconnected-(J4-Pad385)") (class "Default")
      (node (ref "J4") (pin "385") (pinfunction "385_385") (pintype "passive+no_connect"))
    )
    (net (code "218") (name "unconnected-(J4-Pad386)") (class "Default")
      (node (ref "J4") (pin "386") (pinfunction "386_386") (pintype "passive+no_connect"))
    )
    (net (code "219") (name "unconnected-(J4-Pad388)") (class "Default")
      (node (ref "J4") (pin "388") (pinfunction "388_388") (pintype "passive+no_connect"))
    )
    (net (code "220") (name "unconnected-(J4-Pad389)") (class "Default")
      (node (ref "J4") (pin "389") (pinfunction "389_389") (pintype "passive+no_connect"))
    )
    (net (code "221") (name "unconnected-(J4-Pad392)") (class "Default")
      (node (ref "J4") (pin "392") (pinfunction "392_392") (pintype "passive+no_connect"))
    )
    (net (code "222") (name "unconnected-(J4-Pad393)") (class "Default")
      (node (ref "J4") (pin "393") (pinfunction "393_393") (pintype "passive+no_connect"))
    )
    (net (code "223") (name "unconnected-(J4-Pad395)") (class "Default")
      (node (ref "J4") (pin "395") (pinfunction "395_395") (pintype "passive+no_connect"))
    )
    (net (code "224") (name "unconnected-(J4-Pad396)") (class "Default")
      (node (ref "J4") (pin "396") (pinfunction "396_396") (pintype "passive+no_connect"))
    )
    (net (code "225") (name "unconnected-(J4-Pad398)") (class "Default")
      (node (ref "J4") (pin "398") (pinfunction "398_398") (pintype "passive+no_connect"))
    )
    (net (code "226") (name "unconnected-(J4-Pad399)") (class "Default")
      (node (ref "J4") (pin "399") (pinfunction "399_399") (pintype "passive+no_connect"))
    )
    (net (code "227") (name "unconnected-(U61-A-Pad1)") (class "Default")
      (node (ref "U61") (pin "1") (pinfunction "A_1") (pintype "passive"))
    )
    (net (code "228") (name "unconnected-(U61-B-Pad3)") (class "Default")
      (node (ref "U61") (pin "3") (pinfunction "B_3") (pintype "passive"))
    )
    (net (code "229") (name "unconnected-(U61-C-Pad4)") (class "Default")
      (node (ref "U61") (pin "4") (pinfunction "C_4") (pintype "passive+no_connect"))
    )
    (net (code "230") (name "unconnected-(U66-A-Pad1)") (class "Default")
      (node (ref "U66") (pin "1") (pinfunction "A_1") (pintype "passive"))
    )
    (net (code "231") (name "unconnected-(U66-B-Pad3)") (class "Default")
      (node (ref "U66") (pin "3") (pinfunction "B_3") (pintype "passive"))
    )
    (net (code "232") (name "unconnected-(U66-C-Pad4)") (class "Default")
      (node (ref "U66") (pin "4") (pinfunction "C_4") (pintype "passive+no_connect"))
    )
  )
)
